# sram.net
KiCad netlist of a schematic drawn in EAGLE
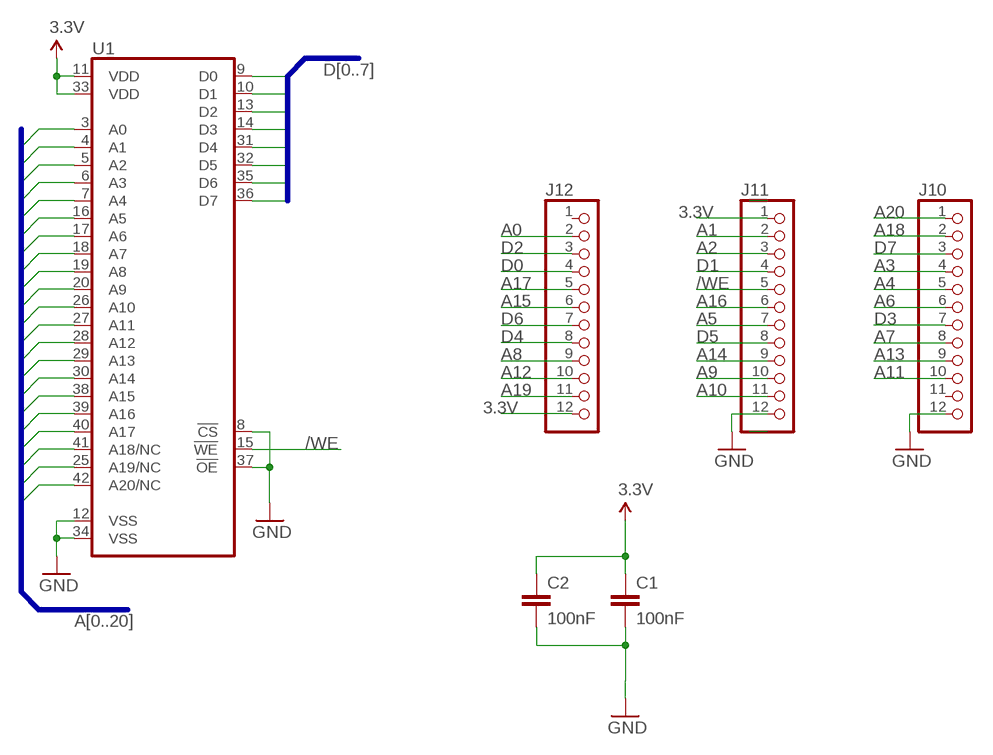
[diagram p0: schematic, sheet 1]

(export (version "E")
  (design (tool "Eeschema 10.0.6"))
  (components
    (comp (ref "C1")
      (value "100nF")
      (footprint "eagle-import:C0805K")
      (libsource (lib "eagle-import") (part "C-EUC0805K"))
    )
    (comp (ref "C2")
      (value "100nF")
      (footprint "eagle-import:C0805K")
      (libsource (lib "eagle-import") (part "C-EUC0805K"))
    )
    (comp (ref "J10")
      (value "PINHD-1X12")
      (footprint "eagle-import:1X12")
      (libsource (lib "eagle-import") (part "PINHD-1X12"))
    )
    (comp (ref "J11")
      (value "PINHD-1X12")
      (footprint "eagle-import:1X12")
      (libsource (lib "eagle-import") (part "PINHD-1X12"))
    )
    (comp (ref "J12")
      (value "PINHD-1X12")
      (footprint "eagle-import:1X12")
      (libsource (lib "eagle-import") (part "PINHD-1X12"))
    )
    (comp (ref "U1")
      (value "ISSI_SRAM_8BIT")
      (footprint "eagle-import:TSOP44-II")
      (libsource (lib "eagle-import") (part "ISSI_SRAM_8BIT"))
    )
  )
  (nets
    (net (code "1") (name "/A0") (class "Default")
      (node (ref "J12") (pin "2") (pinfunction "2_2") (pintype "passive"))
      (node (ref "U1") (pin "3") (pinfunction "A0_3") (pintype "input"))
    )
    (net (code "2") (name "/A1") (class "Default")
      (node (ref "J11") (pin "2") (pinfunction "2_2") (pintype "passive"))
      (node (ref "U1") (pin "4") (pinfunction "A1_4") (pintype "input"))
    )
    (net (code "3") (name "/A2") (class "Default")
      (node (ref "J11") (pin "3") (pinfunction "3_3") (pintype "passive"))
      (node (ref "U1") (pin "5") (pinfunction "A2_5") (pintype "input"))
    )
    (net (code "4") (name "/A3") (class "Default")
      (node (ref "J10") (pin "4") (pinfunction "4_4") (pintype "passive"))
      (node (ref "U1") (pin "6") (pinfunction "A3_6") (pintype "input"))
    )
    (net (code "5") (name "/A4") (class "Default")
      (node (ref "J10") (pin "5") (pinfunction "5_5") (pintype "passive"))
      (node (ref "U1") (pin "7") (pinfunction "A4_7") (pintype "input"))
    )
    (net (code "6") (name "/A5") (class "Default")
      (node (ref "J11") (pin "7") (pinfunction "7_7") (pintype "passive"))
      (node (ref "U1") (pin "16") (pinfunction "A5_16") (pintype "input"))
    )
    (net (code "7") (name "/A6") (class "Default")
      (node (ref "J10") (pin "6") (pinfunction "6_6") (pintype "passive"))
      (node (ref "U1") (pin "17") (pinfunction "A6_17") (pintype "input"))
    )
    (net (code "8") (name "/A7") (class "Default")
      (node (ref "J10") (pin "8") (pinfunction "8_8") (pintype "passive"))
      (node (ref "U1") (pin "18") (pinfunction "A7_18") (pintype "input"))
    )
    (net (code "9") (name "/A8") (class "Default")
      (node (ref "J12") (pin "9") (pinfunction "9_9") (pintype "passive"))
      (node (ref "U1") (pin "19") (pinfunction "A8_19") (pintype "input"))
    )
    (net (code "10") (name "/A9") (class "Default")
      (node (ref "J11") (pin "10") (pinfunction "10_10") (pintype "passive"))
      (node (ref "U1") (pin "20") (pinfunction "A9_20") (pintype "input"))
    )
    (net (code "11") (name "/A10") (class "Default")
      (node (ref "J11") (pin "11") (pinfunction "11_11") (pintype "passive"))
      (node (ref "U1") (pin "26") (pinfunction "A10_26") (pintype "input"))
    )
    (net (code "12") (name "/A11") (class "Default")
      (node (ref "J10") (pin "10") (pinfunction "10_10") (pintype "passive"))
      (node (ref "U1") (pin "27") (pinfunction "A11_27") (pintype "input"))
    )
    (net (code "13") (name "/A12") (class "Default")
      (node (ref "J12") (pin "10") (pinfunction "10_10") (pintype "passive"))
      (node (ref "U1") (pin "28") (pinfunction "A12_28") (pintype "input"))
    )
    (net (code "14") (name "/A13") (class "Default")
      (node (ref "J10") (pin "9") (pinfunction "9_9") (pintype "passive"))
      (node (ref "U1") (pin "29") (pinfunction "A13_29") (pintype "input"))
    )
    (net (code "15") (name "/A14") (class "Default")
      (node (ref "J11") (pin "9") (pinfunction "9_9") (pintype "passive"))
      (node (ref "U1") (pin "30") (pinfunction "A14_30") (pintype "input"))
    )
    (net (code "16") (name "/A15") (class "Default")
      (node (ref "J12") (pin "6") (pinfunction "6_6") (pintype "passive"))
      (node (ref "U1") (pin "38") (pinfunction "A15_38") (pintype "input"))
    )
    (net (code "17") (name "/A16") (class "Default")
      (node (ref "J11") (pin "6") (pinfunction "6_6") (pintype "passive"))
      (node (ref "U1") (pin "39") (pinfunction "A16_39") (pintype "input"))
    )
    (net (code "18") (name "/A17") (class "Default")
      (node (ref "J12") (pin "5") (pinfunction "5_5") (pintype "passive"))
      (node (ref "U1") (pin "40") (pinfunction "A17_40") (pintype "input"))
    )
    (net (code "19") (name "/A18") (class "Default")
      (node (ref "J10") (pin "2") (pinfunction "2_2") (pintype "passive"))
      (node (ref "U1") (pin "41") (pinfunction "A18/NC_41") (pintype "input"))
    )
    (net (code "20") (name "/A19") (class "Default")
      (node (ref "J12") (pin "11") (pinfunction "11_11") (pintype "passive"))
      (node (ref "U1") (pin "25") (pinfunction "A19/NC_25") (pintype "input"))
    )
    (net (code "21") (name "/A20") (class "Default")
      (node (ref "J10") (pin "1") (pinfunction "1_1") (pintype "passive"))
      (node (ref "U1") (pin "42") (pinfunction "A20/NC_42") (pintype "input"))
    )
    (net (code "23") (name "/D0") (class "Default")
      (node (ref "J12") (pin "4") (pinfunction "4_4") (pintype "passive"))
      (node (ref "U1") (pin "9") (pinfunction "D0_9") (pintype "bidirectional"))
    )
    (net (code "24") (name "/D1") (class "Default")
      (node (ref "J11") (pin "4") (pinfunction "4_4") (pintype "passive"))
      (node (ref "U1") (pin "10") (pinfunction "D1_10") (pintype "bidirectional"))
    )
    (net (code "25") (name "/D2") (class "Default")
      (node (ref "J12") (pin "3") (pinfunction "3_3") (pintype "passive"))
      (node (ref "U1") (pin "13") (pinfunction "D2_13") (pintype "bidirectional"))
    )
    (net (code "26") (name "/D3") (class "Default")
      (node (ref "J10") (pin "7") (pinfunction "7_7") (pintype "passive"))
      (node (ref "U1") (pin "14") (pinfunction "D3_14") (pintype "bidirectional"))
    )
    (net (code "27") (name "/D4") (class "Default")
      (node (ref "J12") (pin "8") (pinfunction "8_8") (pintype "passive"))
      (node (ref "U1") (pin "31") (pinfunction "D4_31") (pintype "bidirectional"))
    )
    (net (code "28") (name "/D5") (class "Default")
      (node (ref "J11") (pin "8") (pinfunction "8_8") (pintype "passive"))
      (node (ref "U1") (pin "32") (pinfunction "D5_32") (pintype "bidirectional"))
    )
    (net (code "29") (name "/D6") (class "Default")
      (node (ref "J12") (pin "7") (pinfunction "7_7") (pintype "passive"))
      (node (ref "U1") (pin "35") (pinfunction "D6_35") (pintype "bidirectional"))
    )
    (net (code "30") (name "/D7") (class "Default")
      (node (ref "J10") (pin "3") (pinfunction "3_3") (pintype "passive"))
      (node (ref "U1") (pin "36") (pinfunction "D7_36") (pintype "bidirectional"))
    )
    (net (code "32") (name "/{slash}WE") (class "Default")
      (node (ref "J11") (pin "5") (pinfunction "5_5") (pintype "passive"))
      (node (ref "U1") (pin "15") (pinfunction "~{WE}_15") (pintype "input"))
    )
    (net (code "33") (name "3.3V") (class "Default")
      (node (ref "C1") (pin "1") (pinfunction "1_1") (pintype "passive"))
      (node (ref "C2") (pin "1") (pinfunction "1_1") (pintype "passive"))
      (node (ref "J11") (pin "1") (pinfunction "1_1") (pintype "passive"))
      (node (ref "J12") (pin "12") (pinfunction "12_12") (pintype "passive"))
      (node (ref "U1") (pin "11") (pinfunction "VDD_11") (pintype "input"))
      (node (ref "U1") (pin "33") (pinfunction "VDD_33") (pintype "input"))
    )
    (net (code "34") (name "GND") (class "Default")
      (node (ref "C1") (pin "2") (pinfunction "2_2") (pintype "passive"))
      (node (ref "C2") (pin "2") (pinfunction "2_2") (pintype "passive"))
      (node (ref "J10") (pin "12") (pinfunction "12_12") (pintype "passive"))
      (node (ref "J11") (pin "12") (pinfunction "12_12") (pintype "passive"))
      (node (ref "U1") (pin "12") (pinfunction "VSS_12") (pintype "input"))
      (node (ref "U1") (pin "34") (pinfunction "VSS_34") (pintype "input"))
      (node (ref "U1") (pin "37") (pinfunction "~{OE}_37") (pintype "input"))
      (node (ref "U1") (pin "8") (pinfunction "~{CS}_8") (pintype "input"))
    )
    (net (code "35") (name "unconnected-(J10-Pad11)") (class "Default")
      (node (ref "J10") (pin "11") (pinfunction "11_11") (pintype "passive"))
    )
    (net (code "36") (name "unconnected-(J12-Pad1)") (class "Default")
      (node (ref "J12") (pin "1") (pinfunction "1_1") (pintype "passive"))
    )
  )
)
